# file-1764160802765-894161147.net
KiCad netlist of a schematic drawn in EAGLE
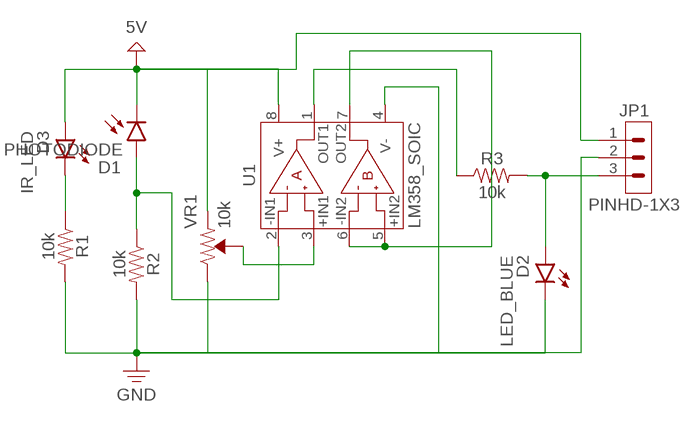
[diagram p0: schematic, sheet 1]

(export (version "E")
  (design (tool "Eeschema 10.0.6"))
  (components
    (comp (ref "D1")
      (value "PHOTODIODE")
      (footprint "eagle-import:LEDRD254W51D580H541B")
      (libsource (lib "eagle-import") (part "PHOTODIODE"))
    )
    (comp (ref "D2")
      (value "LED_BLUE")
      (footprint "eagle-import:LEDRD254W60D565H860B_B")
      (libsource (lib "eagle-import") (part "LED_RADIALBLUE_"))
    )
    (comp (ref "D3")
      (value "IR_LED")
      (footprint "eagle-import:LEDRD254W60D565H860B_B")
      (libsource (lib "eagle-import") (part "LED_RADIALBLUE_"))
    )
    (comp (ref "JP1")
      (value "PINHD-1X3")
      (footprint "eagle-import:1X03")
      (libsource (lib "eagle-import") (part "PINHD-1X3"))
    )
    (comp (ref "R1")
      (value "10k")
      (footprint "eagle-import:AXIAL-0.3")
      (libsource (lib "eagle-import") (part "100KOHM-HORIZ-1/4W-1%"))
    )
    (comp (ref "R2")
      (value "10k")
      (footprint "eagle-import:AXIAL-0.3")
      (libsource (lib "eagle-import") (part "100KOHM-HORIZ-1/4W-1%"))
    )
    (comp (ref "R3")
      (value "10k")
      (footprint "eagle-import:AXIAL-0.3")
      (libsource (lib "eagle-import") (part "100KOHM-HORIZ-1/4W-1%"))
    )
    (comp (ref "U1")
      (value "LM358_SOIC")
      (footprint "eagle-import:SOIC127P600X175-8N")
      (libsource (lib "eagle-import") (part "LM358_SOIC"))
    )
    (comp (ref "VR1")
      (value "10k")
      (footprint "eagle-import:TRIMPOT-PTH-3386U")
      (libsource (lib "eagle-import") (part "TRIMPOT-PTH-10MM-KNOB-1/2W-10%"))
    )
  )
  (nets
    (net (code "1") (name "5V") (class "Default")
      (node (ref "D1") (pin "C") (pinfunction "C_C") (pintype "passive"))
      (node (ref "D3") (pin "1") (pinfunction "A_1") (pintype "passive"))
      (node (ref "JP1") (pin "1") (pinfunction "1_1") (pintype "passive"))
      (node (ref "U1") (pin "8") (pinfunction "V+_8") (pintype "bidirectional"))
      (node (ref "VR1") (pin "1") (pinfunction "CCW_1") (pintype "passive"))
    )
    (net (code "2") (name "GND") (class "Default")
      (node (ref "D2") (pin "2") (pinfunction "C_2") (pintype "passive"))
      (node (ref "JP1") (pin "2") (pinfunction "2_2") (pintype "passive"))
      (node (ref "R1") (pin "P$2") (pinfunction "2_P$2") (pintype "passive"))
      (node (ref "R2") (pin "P$2") (pinfunction "2_P$2") (pintype "passive"))
      (node (ref "U1") (pin "4") (pinfunction "V-_4") (pintype "bidirectional"))
      (node (ref "VR1") (pin "3") (pinfunction "CW_3") (pintype "passive"))
    )
    (net (code "3") (name "Net-(D2-A)") (class "Default")
      (node (ref "D2") (pin "1") (pinfunction "A_1") (pintype "passive"))
      (node (ref "JP1") (pin "3") (pinfunction "3_3") (pintype "passive"))
      (node (ref "R3") (pin "P$2") (pinfunction "2_P$2") (pintype "passive"))
    )
    (net (code "4") (name "Net-(D3-C)") (class "Default")
      (node (ref "D3") (pin "2") (pinfunction "C_2") (pintype "passive"))
      (node (ref "R1") (pin "P$1") (pinfunction "1_P$1") (pintype "passive"))
    )
    (net (code "5") (name "Net-(R2-1)") (class "Default")
      (node (ref "D1") (pin "A") (pinfunction "A_A") (pintype "passive"))
      (node (ref "R2") (pin "P$1") (pinfunction "1_P$1") (pintype "passive"))
      (node (ref "U1") (pin "2") (pinfunction "-IN1_2") (pintype "input"))
    )
    (net (code "6") (name "Net-(R3-1)") (class "Default")
      (node (ref "R3") (pin "P$1") (pinfunction "1_P$1") (pintype "passive"))
      (node (ref "U1") (pin "1") (pinfunction "OUT1_1") (pintype "output"))
    )
    (net (code "7") (name "Net-(U1-+IN1)") (class "Default")
      (node (ref "U1") (pin "3") (pinfunction "+IN1_3") (pintype "input"))
      (node (ref "VR1") (pin "2") (pinfunction "WIPER_2") (pintype "passive"))
    )
    (net (code "8") (name "Net-(U1-+IN2)") (class "Default")
      (node (ref "U1") (pin "5") (pinfunction "+IN2_5") (pintype "input"))
      (node (ref "U1") (pin "6") (pinfunction "-IN2_6") (pintype "input"))
      (node (ref "U1") (pin "7") (pinfunction "OUT2_7") (pintype "output"))
    )
  )
)
